# HV9150_DevKit.net
KiCad netlist of a schematic drawn in Altium Designer
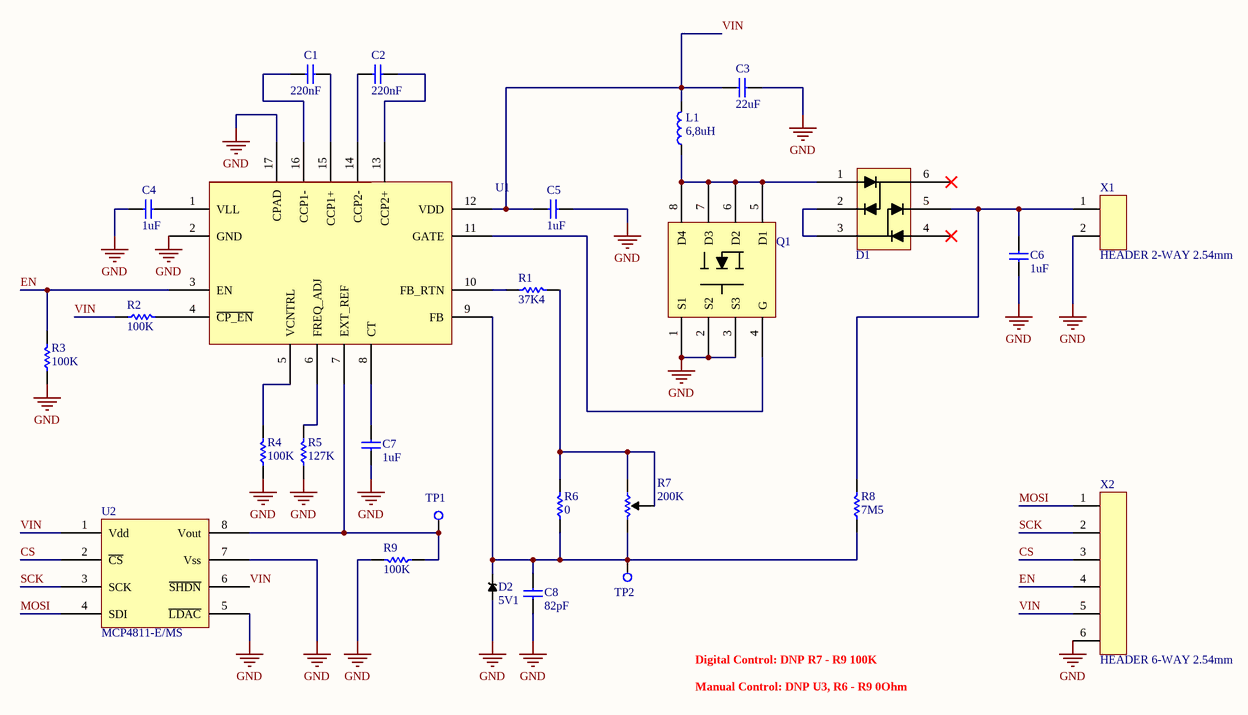
[diagram p0: HV9150 DevKit.SchDoc]

(export (version "E")
  (design (tool "Eeschema 10.0.6"))
  (components
    (comp (ref "C1")
      (value "220nF")
      (footprint "CAP 0805/2012")
      (description "CAPACITOR 220nF 0805 20%16V")
      (fields
        (field (name "MANUFACTURER") "Kyocera AVX")
        (field (name "MANUFACTURER PART NUMBER") "0805YC224MAT2A")
      )
      (libsource (lib "Ultrasound") (part "0805YC224MAT2A"))
    )
    (comp (ref "C2")
      (value "220nF")
      (footprint "CAP 0805/2012")
      (description "CAPACITOR 220nF 0805 20%16V")
      (fields
        (field (name "MANUFACTURER") "Kyocera AVX")
        (field (name "MANUFACTURER PART NUMBER") "0805YC224MAT2A")
      )
      (libsource (lib "Ultrasound") (part "0805YC224MAT2A"))
    )
    (comp (ref "C3")
      (value "22uF")
      (footprint "CAP 1206/3216")
      (description "CAPACITOR 22uF 1206 20% 16V")
      (fields
        (field (name "MANUFACTURER") "Kyocera AVX")
        (field (name "MANUFACTURER PART NUMBER") "F931C226MAA")
      )
      (libsource (lib "Ultrasound") (part "F931C226MAA"))
    )
    (comp (ref "C4")
      (value "1uF")
      (footprint "CAP 0805/2012")
      (description "CAPACITOR 1uF 0805 10% 16V")
      (fields
        (field (name "MANUFACTURER") "Yageo")
        (field (name "MANUFACTURER PART NUMBER") "CC0805KKX7R7BB105")
      )
      (libsource (lib "Ultrasound") (part "CC0805KKX7R7BB105"))
    )
    (comp (ref "C5")
      (value "1uF")
      (footprint "CAP 0805/2012")
      (description "CAPACITOR 1uF 0805 10% 16V")
      (fields
        (field (name "MANUFACTURER") "Yageo")
        (field (name "MANUFACTURER PART NUMBER") "CC0805KKX7R7BB105")
      )
      (libsource (lib "Ultrasound") (part "CC0805KKX7R7BB105"))
    )
    (comp (ref "C6")
      (value "1uF")
      (footprint "CAP 2220/5650")
      (description "CAPACITOR 1uF 2220 20% 500V")
      (fields
        (field (name "MANUFACTURER") "KEMET")
        (field (name "MANUFACTURER PART NUMBER") "C2220C105MCR2C7186")
      )
      (libsource (lib "Ultrasound") (part "C2220C105MCR2C7186"))
    )
    (comp (ref "C7")
      (value "1uF")
      (footprint "CAP 0805/2012")
      (description "CAPACITOR 1uF 0805 10% 16V")
      (fields
        (field (name "MANUFACTURER") "Yageo")
        (field (name "MANUFACTURER PART NUMBER") "CC0805KKX7R7BB105")
      )
      (libsource (lib "Ultrasound") (part "CC0805KKX7R7BB105"))
    )
    (comp (ref "C8")
      (value "82pF")
      (footprint "CAP 0805/2012")
      (description "CAPACITOR 82pF 0805 5% 50V")
      (fields
        (field (name "MANUFACTURER") "Multicomp")
        (field (name "MANUFACTURER PART NUMBER") "MC0805N820K500CT")
      )
      (libsource (lib "Ultrasound") (part "MC0805N820K500CT"))
    )
    (comp (ref "D1")
      (value "BAV99S,115")
      (footprint "SOT-363")
      (description "BAV99S Diodes 100 V")
      (fields (field (name "MANUFACTURER") "NXP Semiconductors") (field (name "VOLTAGE") "75V"))
      (libsource (lib "Ultrasound") (part "BAV99S,115"))
    )
    (comp (ref "D2")
      (value "5V1")
      (footprint "DZ2705100L -  Diodo Zener")
      (description "ZENER Diode 5V1")
      (fields
        (field (name "MANUFACTURER") "Panasonic SSG")
        (field (name "MANUFACTURER PART NUMBER") "DZ2705100L")
      )
      (libsource (lib "Ultrasound") (part "DZ2705100L"))
    )
    (comp (ref "L1")
      (value "6,8uH")
      (footprint "WE-LHMI_4020")
      (description "INDUCTOR 6,8 uH 20% 1,75 A")
      (fields
        (field (name "MANUFACTURER") "Wurth Electronics")
        (field (name "MANUFACTURER PART NUMBER") "74437324068")
      )
      (libsource (lib "Ultrasound") (part "74437324068"))
    )
    (comp (ref "Q1")
      (value "BSZ42DN25NS3G")
      (footprint "BSZ42DN25NS3")
      (description "BSZ42DN25NS3G 250 V MOSFET")
      (fields (field (name "MANUFACTURER") "Infineon"))
      (libsource (lib "Ultrasound") (part "BSZ42DN25NS3G"))
    )
    (comp (ref "R1")
      (value "37K4")
      (footprint "RES 0805/2012")
      (description "RESISTOR 37K4 0805 1% 1/8mW")
      (fields
        (field (name "MANUFACTURER") "Panasonic")
        (field (name "MANUFACTURER PART NUMBER") "ERJ-6ENF3742V")
      )
      (libsource (lib "Ultrasound") (part "ERJ6ENF3742V"))
    )
    (comp (ref "R2")
      (value "100K")
      (footprint "RES 0805/2012")
      (description "RESISTOR 100K 0805 1% 1/8W")
      (fields
        (field (name "MANUFACTURER") "Panasonic")
        (field (name "MANUFACTURER PART NUMBER") "ERJ-6ENF1003V")
      )
      (libsource (lib "Ultrasound") (part "ERJ-6ENF1003V"))
    )
    (comp (ref "R3")
      (value "100K")
      (footprint "RES 0805/2012")
      (description "RESISTOR 100K 0805 1% 1/8W")
      (fields
        (field (name "MANUFACTURER") "Panasonic")
        (field (name "MANUFACTURER PART NUMBER") "ERJ-6ENF1003V")
      )
      (libsource (lib "Ultrasound") (part "ERJ-6ENF1003V"))
    )
    (comp (ref "R4")
      (value "100K")
      (footprint "RES 0805/2012")
      (description "RESISTOR 100K 0805 1% 1/8W")
      (fields
        (field (name "MANUFACTURER") "Panasonic")
        (field (name "MANUFACTURER PART NUMBER") "ERJ-6ENF1003V")
      )
      (libsource (lib "Ultrasound") (part "ERJ-6ENF1003V"))
    )
    (comp (ref "R5")
      (value "127K")
      (footprint "RES 0805/2012")
      (description "RESISTOR 127K 0805 1% 1/8mW")
      (fields
        (field (name "MANUFACTURER") "Panasonic")
        (field (name "MANUFACTURER PART NUMBER") "ERJ6ENF1273V")
      )
      (libsource (lib "Ultrasound") (part "ERJ6ENF1273V"))
    )
    (comp (ref "R6")
      (value "0")
      (footprint "RES 0805/2012")
      (description "RESISTOR 0K 0805 1% 1/8mW")
      (fields
        (field (name "MANUFACTURER") "Vishay Dale")
        (field (name "MANUFACTURER PART NUMBER") "CRCW08050000Z0ECC")
      )
      (libsource (lib "Ultrasound") (part "CRCW08050000Z0ECC"))
    )
    (comp (ref "R7")
      (value "200K")
      (footprint "BOURNS 3386F")
      (description "POT 200K 3386F 10% 500mW trimmer potentiometer")
      (fields
        (field (name "MANUFACTURER") "Bourns")
        (field (name "MANUFACTURER PART NUMBER") "3386F-1-204TLF")
      )
      (libsource (lib "Ultrasound") (part "3386F-1-204TLF"))
    )
    (comp (ref "R8")
      (value "7M5")
      (footprint "RES 1206/3216")
      (description "RESISTOR 7M5, 1206, 1%, 0.25W,  500V")
      (fields
        (field (name "MANUFACTURER") "Multicomp")
        (field (name "MANUFACTURER PART NUMBER") "MCHVR06FTFV7504")
      )
      (libsource (lib "Ultrasound") (part "MCHVR06FTFV7504"))
    )
    (comp (ref "R9")
      (value "100K")
      (footprint "RES 0805/2012")
      (description "RESISTOR 100K 0805 1% 1/8W")
      (fields
        (field (name "MANUFACTURER") "Panasonic")
        (field (name "MANUFACTURER PART NUMBER") "ERJ-6ENF1003V")
      )
      (libsource (lib "Ultrasound") (part "ERJ-6ENF1003V"))
    )
    (comp (ref "TP1")
      (value "TESTPOINT")
      (footprint "TP_SMD_Ø1.0mm")
      (libsource (lib "Ultrasound") (part "TESTPOINT"))
    )
    (comp (ref "TP2")
      (value "TESTPOINT")
      (footprint "TP_SMD_Ø1.0mm")
      (libsource (lib "Ultrasound") (part "TESTPOINT"))
    )
    (comp (ref "U1")
      (value "HV9150K6-G")
      (footprint "QFN16 3X3")
      (fields (field (name "MANUFACTURER") "Microchip Supertex"))
      (libsource (lib "Ultrasound") (part "HV9150K6-G"))
    )
    (comp (ref "U2")
      (value "MCP4811-E/MS")
      (footprint "MSOP8")
      (fields (field (name "MANUFACTURER") "Microchip"))
      (libsource (lib "Ultrasound") (part "MCP4811-E/MS"))
    )
    (comp (ref "X1")
      (value "HEADER 2-WAY 2.54mm")
      (footprint "HEADER 2-WAY 2.54 mm")
      (description "HEADER 2-WAY")
      (libsource (lib "Ultrasound") (part "HEADER 2-WAY 2.54mm"))
    )
    (comp (ref "X2")
      (value "HEADER 6-WAY 2.54mm")
      (footprint "HEADER 6-WAY 2.54 mm")
      (description "HEADER 6-WAY")
      (libsource (lib "Ultrasound") (part "HEADER 6-WAY 2.54mm"))
    )
  )
  (nets
    (net (code "1") (name "/CS") (class "Default")
      (node (ref "U2") (pin "2") (pinfunction "~{CS}_2") (pintype "passive"))
      (node (ref "X2") (pin "3") (pinfunction "3_3") (pintype "passive"))
    )
    (net (code "2") (name "/EN") (class "Default")
      (node (ref "R3") (pin "2") (pintype "passive"))
      (node (ref "U1") (pin "3") (pinfunction "EN_3") (pintype "passive"))
      (node (ref "X2") (pin "4") (pinfunction "4_4") (pintype "passive"))
    )
    (net (code "3") (name "/MOSI") (class "Default")
      (node (ref "U2") (pin "4") (pinfunction "SDI_4") (pintype "passive"))
      (node (ref "X2") (pin "1") (pinfunction "1_1") (pintype "passive"))
    )
    (net (code "4") (name "/SCK") (class "Default")
      (node (ref "U2") (pin "3") (pinfunction "SCK_3") (pintype "passive"))
      (node (ref "X2") (pin "2") (pinfunction "2_2") (pintype "passive"))
    )
    (net (code "5") (name "/VIN") (class "Default")
      (node (ref "C3") (pin "1") (pinfunction "1_1") (pintype "passive"))
      (node (ref "C5") (pin "2") (pinfunction "2_2") (pintype "passive"))
      (node (ref "L1") (pin "2") (pinfunction "2_2") (pintype "passive"))
      (node (ref "R2") (pin "1") (pintype "passive"))
      (node (ref "U1") (pin "12") (pinfunction "VDD_12") (pintype "passive"))
      (node (ref "U2") (pin "1") (pinfunction "Vdd_1") (pintype "passive"))
      (node (ref "U2") (pin "6") (pinfunction "~{SHDN}_6") (pintype "passive"))
      (node (ref "X2") (pin "5") (pinfunction "5_5") (pintype "passive"))
    )
    (net (code "6") (name "GND") (class "Default")
      (node (ref "C3") (pin "2") (pinfunction "2_2") (pintype "passive"))
      (node (ref "C4") (pin "1") (pinfunction "1_1") (pintype "passive"))
      (node (ref "C5") (pin "1") (pinfunction "1_1") (pintype "passive"))
      (node (ref "C6") (pin "1") (pinfunction "1_1") (pintype "passive"))
      (node (ref "C7") (pin "1") (pinfunction "1_1") (pintype "passive"))
      (node (ref "C8") (pin "1") (pinfunction "1_1") (pintype "passive"))
      (node (ref "D2") (pin "1") (pinfunction "A_1") (pintype "passive"))
      (node (ref "Q1") (pin "1") (pinfunction "S1_1") (pintype "passive"))
      (node (ref "Q1") (pin "2") (pinfunction "S2_2") (pintype "passive"))
      (node (ref "Q1") (pin "3") (pinfunction "S3_3") (pintype "passive"))
      (node (ref "R3") (pin "1") (pintype "passive"))
      (node (ref "R4") (pin "1") (pintype "passive"))
      (node (ref "R5") (pin "1") (pintype "passive"))
      (node (ref "R9") (pin "2") (pintype "passive"))
      (node (ref "U1") (pin "17") (pinfunction "CPAD_17") (pintype "passive"))
      (node (ref "U1") (pin "2") (pinfunction "GND_2") (pintype "passive"))
      (node (ref "U2") (pin "5") (pinfunction "~{LDAC}_5") (pintype "passive"))
      (node (ref "U2") (pin "7") (pinfunction "Vss_7") (pintype "passive"))
      (node (ref "X1") (pin "2") (pinfunction "2_2") (pintype "passive"))
      (node (ref "X2") (pin "6") (pinfunction "6_6") (pintype "passive"))
    )
    (net (code "7") (name "Net-(C6-Pad2)") (class "Default")
      (node (ref "C6") (pin "2") (pinfunction "2_2") (pintype "passive"))
      (node (ref "D1") (pin "5") (pinfunction "5_5") (pintype "passive"))
      (node (ref "R8") (pin "2") (pintype "passive"))
      (node (ref "X1") (pin "1") (pinfunction "1_1") (pintype "passive"))
    )
    (net (code "8") (name "Net-(D1-Pad2)") (class "Default")
      (node (ref "D1") (pin "2") (pinfunction "2_2") (pintype "passive"))
      (node (ref "D1") (pin "3") (pinfunction "3_3") (pintype "passive"))
    )
    (net (code "9") (name "Net-(D2-K)") (class "Default")
      (node (ref "C8") (pin "2") (pinfunction "2_2") (pintype "passive"))
      (node (ref "D2") (pin "2") (pinfunction "K_2") (pintype "passive"))
      (node (ref "R6") (pin "1") (pintype "passive"))
      (node (ref "R7") (pin "3") (pintype "passive"))
      (node (ref "R8") (pin "1") (pintype "passive"))
      (node (ref "TP2") (pin "1") (pinfunction "TP_1") (pintype "passive"))
      (node (ref "U1") (pin "9") (pinfunction "FB_9") (pintype "passive"))
    )
    (net (code "10") (name "Net-(Q1-D1)") (class "Default")
      (node (ref "D1") (pin "1") (pinfunction "1_1") (pintype "passive"))
      (node (ref "L1") (pin "1") (pinfunction "1_1") (pintype "passive"))
      (node (ref "Q1") (pin "5") (pinfunction "D1_5") (pintype "passive"))
      (node (ref "Q1") (pin "6") (pinfunction "D2_6") (pintype "passive"))
      (node (ref "Q1") (pin "7") (pinfunction "D3_7") (pintype "passive"))
      (node (ref "Q1") (pin "8") (pinfunction "D4_8") (pintype "passive"))
    )
    (net (code "11") (name "Net-(Q1-G)") (class "Default")
      (node (ref "Q1") (pin "4") (pinfunction "G_4") (pintype "passive"))
      (node (ref "U1") (pin "11") (pinfunction "GATE_11") (pintype "passive"))
    )
    (net (code "12") (name "Net-(R1-Pad2)") (class "Default")
      (node (ref "R1") (pin "2") (pintype "passive"))
      (node (ref "R6") (pin "2") (pintype "passive"))
      (node (ref "R7") (pin "1") (pintype "passive"))
      (node (ref "R7") (pin "2") (pintype "passive"))
    )
    (net (code "13") (name "Net-(TP1-TP)") (class "Default")
      (node (ref "R9") (pin "1") (pintype "passive"))
      (node (ref "TP1") (pin "1") (pinfunction "TP_1") (pintype "passive"))
      (node (ref "U1") (pin "7") (pinfunction "EXT_REF_7") (pintype "passive"))
      (node (ref "U2") (pin "8") (pinfunction "Vout_8") (pintype "passive"))
    )
    (net (code "14") (name "Net-(U1-CCP1+)") (class "Default")
      (node (ref "C1") (pin "2") (pinfunction "2_2") (pintype "passive"))
      (node (ref "U1") (pin "15") (pinfunction "CCP1+_15") (pintype "passive"))
    )
    (net (code "15") (name "Net-(U1-CCP1-)") (class "Default")
      (node (ref "C1") (pin "1") (pinfunction "1_1") (pintype "passive"))
      (node (ref "U1") (pin "16") (pinfunction "CCP1-_16") (pintype "passive"))
    )
    (net (code "16") (name "Net-(U1-CCP2+)") (class "Default")
      (node (ref "C2") (pin "2") (pinfunction "2_2") (pintype "passive"))
      (node (ref "U1") (pin "13") (pinfunction "CCP2+_13") (pintype "passive"))
    )
    (net (code "17") (name "Net-(U1-CCP2-)") (class "Default")
      (node (ref "C2") (pin "1") (pinfunction "1_1") (pintype "passive"))
      (node (ref "U1") (pin "14") (pinfunction "CCP2-_14") (pintype "passive"))
    )
    (net (code "18") (name "Net-(U1-CT)") (class "Default")
      (node (ref "C7") (pin "2") (pinfunction "2_2") (pintype "passive"))
      (node (ref "U1") (pin "8") (pinfunction "CT_8") (pintype "passive"))
    )
    (net (code "19") (name "Net-(U1-FB_RTN)") (class "Default")
      (node (ref "R1") (pin "1") (pintype "passive"))
      (node (ref "U1") (pin "10") (pinfunction "FB_RTN_10") (pintype "passive"))
    )
    (net (code "20") (name "Net-(U1-FREQ_ADJ)") (class "Default")
      (node (ref "R5") (pin "2") (pintype "passive"))
      (node (ref "U1") (pin "6") (pinfunction "FREQ_ADJ_6") (pintype "passive"))
    )
    (net (code "21") (name "Net-(U1-VCNTRL)") (class "Default")
      (node (ref "R4") (pin "2") (pintype "passive"))
      (node (ref "U1") (pin "5") (pinfunction "VCNTRL_5") (pintype "passive"))
    )
    (net (code "22") (name "Net-(U1-VLL)") (class "Default")
      (node (ref "C4") (pin "2") (pinfunction "2_2") (pintype "passive"))
      (node (ref "U1") (pin "1") (pinfunction "VLL_1") (pintype "passive"))
    )
    (net (code "23") (name "Net-(U1-~{CP_EN})") (class "Default")
      (node (ref "R2") (pin "2") (pintype "passive"))
      (node (ref "U1") (pin "4") (pinfunction "~{CP_EN}_4") (pintype "passive"))
    )
    (net (code "24") (name "unconnected-(D1-Pad4)") (class "Default")
      (node (ref "D1") (pin "4") (pinfunction "4_4") (pintype "passive+no_connect"))
    )
    (net (code "25") (name "unconnected-(D1-Pad6)") (class "Default")
      (node (ref "D1") (pin "6") (pinfunction "6_6") (pintype "passive+no_connect"))
    )
  )
)
